# Schematic.net
KiCad netlist of a schematic drawn in Altium Designer
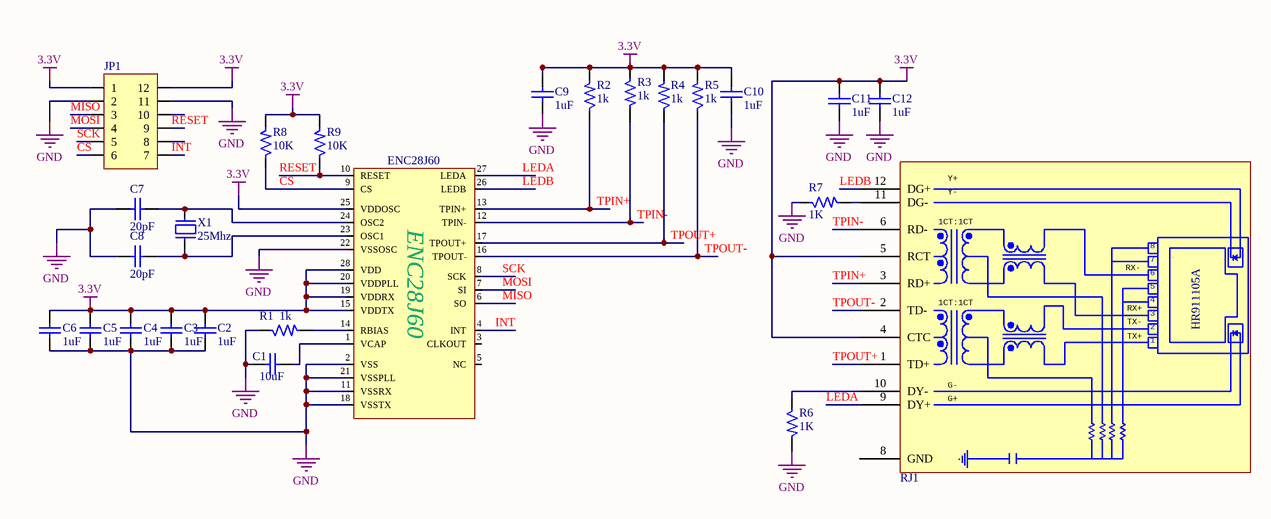
[diagram p0: Schematic.SchDoc]

(export (version "E")
  (design (tool "Eeschema 10.0.6"))
  (components
    (comp (ref "C1")
      (value "10uF")
      (footprint "CAP_0805")
      (description "Capacitor")
      (fields (field (name "PUBLISHER") "Altium Limited"))
      (libsource (lib "library") (part "CapSMD"))
    )
    (comp (ref "C2")
      (value "1uF")
      (footprint "CAP_0805")
      (description "Capacitor")
      (fields (field (name "PUBLISHER") "Altium Limited"))
      (libsource (lib "library") (part "CapSMD"))
    )
    (comp (ref "C3")
      (value "1uF")
      (footprint "CAP_0805")
      (description "Capacitor")
      (fields (field (name "PUBLISHER") "Altium Limited"))
      (libsource (lib "library") (part "CapSMD"))
    )
    (comp (ref "C4")
      (value "1uF")
      (footprint "CAP_0805")
      (description "Capacitor")
      (fields (field (name "PUBLISHER") "Altium Limited"))
      (libsource (lib "library") (part "CapSMD"))
    )
    (comp (ref "C5")
      (value "1uF")
      (footprint "CAP_0805")
      (description "Capacitor")
      (fields (field (name "PUBLISHER") "Altium Limited"))
      (libsource (lib "library") (part "CapSMD"))
    )
    (comp (ref "C6")
      (value "1uF")
      (footprint "CAP_0805")
      (description "Capacitor")
      (fields (field (name "PUBLISHER") "Altium Limited"))
      (libsource (lib "library") (part "CapSMD"))
    )
    (comp (ref "C7")
      (value "20pF")
      (footprint "CAP_0805")
      (description "Capacitor")
      (fields (field (name "PUBLISHER") "Altium Limited"))
      (libsource (lib "library") (part "CapSMD"))
    )
    (comp (ref "C8")
      (value "20pF")
      (footprint "CAP_0805")
      (description "Capacitor")
      (fields (field (name "PUBLISHER") "Altium Limited"))
      (libsource (lib "library") (part "CapSMD"))
    )
    (comp (ref "C9")
      (value "1uF")
      (footprint "CAP_0805")
      (description "Capacitor")
      (fields (field (name "PUBLISHER") "Altium Limited"))
      (libsource (lib "library") (part "CapSMD"))
    )
    (comp (ref "C10")
      (value "1uF")
      (footprint "CAP_0805")
      (description "Capacitor")
      (fields (field (name "PUBLISHER") "Altium Limited"))
      (libsource (lib "library") (part "CapSMD"))
    )
    (comp (ref "C11")
      (value "1uF")
      (footprint "CAP_0805")
      (description "Capacitor")
      (fields (field (name "PUBLISHER") "Altium Limited"))
      (libsource (lib "library") (part "CapSMD"))
    )
    (comp (ref "C12")
      (value "1uF")
      (footprint "CAP_0805")
      (description "Capacitor")
      (fields (field (name "PUBLISHER") "Altium Limited"))
      (libsource (lib "library") (part "CapSMD"))
    )
    (comp (ref "ENC28J60")
      (value "ENC28J60?")
      (footprint "SOP_28M_127")
      (libsource (lib "library") (part "ENC28J60"))
    )
    (comp (ref "JP1")
      (value "JP6x2")
      (footprint "JP6-D2T")
      (description "WR-PHD 2.54 mm Dual Socket Header")
      (fields
        (field (name "MANUFACTURER") "Würth Elektronik eiSos GmbH")
        (field (name "PARTNO") "61301221821")
        (field (name "CREATED BY") "Karrer Zheng")
      )
      (libsource (lib "LIBRARY") (part "JP6x2"))
    )
    (comp (ref "R1")
      (value "1k")
      (footprint "RES_0805")
      (description "Resistor 1/4W")
      (libsource (lib "library") (part "Res_0805"))
    )
    (comp (ref "R2")
      (value "1k")
      (footprint "RES_0805")
      (description "Resistor 1/4W")
      (libsource (lib "library") (part "Res_0805"))
    )
    (comp (ref "R3")
      (value "1k")
      (footprint "RES_0805")
      (description "Resistor 1/4W")
      (libsource (lib "library") (part "Res_0805"))
    )
    (comp (ref "R4")
      (value "1k")
      (footprint "RES_0805")
      (description "Resistor 1/4W")
      (libsource (lib "library") (part "Res_0805"))
    )
    (comp (ref "R5")
      (value "1k")
      (footprint "RES_0805")
      (description "Resistor 1/4W")
      (libsource (lib "library") (part "Res_0805"))
    )
    (comp (ref "R6")
      (value "1K")
      (footprint "RES_0805")
      (description "Resistor 1/4W")
      (libsource (lib "library") (part "Res_0805"))
    )
    (comp (ref "R7")
      (value "1K")
      (footprint "RES_0805")
      (description "Resistor 1/4W")
      (libsource (lib "library") (part "Res_0805"))
    )
    (comp (ref "R8")
      (value "10K")
      (footprint "RES_0805")
      (description "Resistor 1/4W")
      (libsource (lib "library") (part "Res_0805"))
    )
    (comp (ref "R9")
      (value "10K")
      (footprint "RES_0805")
      (description "Resistor 1/4W")
      (libsource (lib "library") (part "Res_0805"))
    )
    (comp (ref "RJ1") (value "RJ45") (footprint "RJ45") (libsource (lib "library") (part "RJ45-Con")))
    (comp (ref "X1")
      (value "25Mhz")
      (footprint "XT2")
      (description "Crystal, 32.768 KHz, -40 to 85 degC, 3.2 x 1.5 x 0.9 mm SMD")
      (libsource (lib "LIBRARY") (part "XT2"))
    )
  )
  (nets
    (net (code "2") (name "/CS") (class "Default")
      (node (ref "ENC28J60") (pin "9") (pinfunction "CS_9") (pintype "passive"))
      (node (ref "JP1") (pin "6") (pinfunction "6_6") (pintype "passive"))
      (node (ref "R8") (pin "1") (pinfunction "1_1") (pintype "passive"))
    )
    (net (code "3") (name "/INT") (class "Default")
      (node (ref "ENC28J60") (pin "4") (pinfunction "INT_4") (pintype "passive"))
      (node (ref "JP1") (pin "7") (pinfunction "7_7") (pintype "passive"))
    )
    (net (code "4") (name "/LEDA") (class "Default")
      (node (ref "ENC28J60") (pin "27") (pinfunction "LEDA_27") (pintype "passive"))
      (node (ref "RJ1") (pin "9") (pinfunction "DY+_9") (pintype "passive"))
    )
    (net (code "5") (name "/LEDB") (class "Default")
      (node (ref "ENC28J60") (pin "26") (pinfunction "LEDB_26") (pintype "passive"))
      (node (ref "RJ1") (pin "12") (pinfunction "DG+_12") (pintype "passive"))
    )
    (net (code "6") (name "/MISO") (class "Default")
      (node (ref "ENC28J60") (pin "6") (pinfunction "SO_6") (pintype "passive"))
      (node (ref "JP1") (pin "3") (pinfunction "3_3") (pintype "passive"))
    )
    (net (code "7") (name "/MOSI") (class "Default")
      (node (ref "ENC28J60") (pin "7") (pinfunction "SI_7") (pintype "passive"))
      (node (ref "JP1") (pin "4") (pinfunction "4_4") (pintype "passive"))
    )
    (net (code "8") (name "/RESET") (class "Default")
      (node (ref "ENC28J60") (pin "10") (pinfunction "RESET_10") (pintype "passive"))
      (node (ref "JP1") (pin "9") (pinfunction "9_9") (pintype "passive"))
      (node (ref "R9") (pin "1") (pinfunction "1_1") (pintype "passive"))
    )
    (net (code "9") (name "/SCK") (class "Default")
      (node (ref "ENC28J60") (pin "8") (pinfunction "SCK_8") (pintype "passive"))
      (node (ref "JP1") (pin "5") (pinfunction "5_5") (pintype "passive"))
    )
    (net (code "10") (name "/TPIN+") (class "Default")
      (node (ref "ENC28J60") (pin "13") (pinfunction "TPIN+_13") (pintype "passive"))
      (node (ref "R2") (pin "1") (pinfunction "1_1") (pintype "passive"))
      (node (ref "RJ1") (pin "3") (pinfunction "RD+_3") (pintype "passive"))
    )
    (net (code "11") (name "/TPIN-") (class "Default")
      (node (ref "ENC28J60") (pin "12") (pinfunction "TPIN-_12") (pintype "passive"))
      (node (ref "R3") (pin "2") (pinfunction "2_2") (pintype "passive"))
      (node (ref "RJ1") (pin "6") (pinfunction "RD-_6") (pintype "passive"))
    )
    (net (code "12") (name "/TPOUT+") (class "Default")
      (node (ref "ENC28J60") (pin "17") (pinfunction "TPOUT+_17") (pintype "passive"))
      (node (ref "R4") (pin "1") (pinfunction "1_1") (pintype "passive"))
      (node (ref "RJ1") (pin "1") (pinfunction "TD+_1") (pintype "passive"))
    )
    (net (code "13") (name "/TPOUT-") (class "Default")
      (node (ref "ENC28J60") (pin "16") (pinfunction "TPOUT-_16") (pintype "passive"))
      (node (ref "R5") (pin "1") (pinfunction "1_1") (pintype "passive"))
      (node (ref "RJ1") (pin "2") (pinfunction "TD-_2") (pintype "passive"))
    )
    (net (code "14") (name "3.3V") (class "Default")
      (node (ref "C10") (pin "1") (pinfunction "1_1") (pintype "passive"))
      (node (ref "C11") (pin "1") (pinfunction "1_1") (pintype "passive"))
      (node (ref "C12") (pin "1") (pinfunction "1_1") (pintype "passive"))
      (node (ref "C2") (pin "1") (pinfunction "1_1") (pintype "passive"))
      (node (ref "C3") (pin "1") (pinfunction "1_1") (pintype "passive"))
      (node (ref "C4") (pin "2") (pinfunction "2_2") (pintype "passive"))
      (node (ref "C5") (pin "1") (pinfunction "1_1") (pintype "passive"))
      (node (ref "C6") (pin "1") (pinfunction "1_1") (pintype "passive"))
      (node (ref "C9") (pin "2") (pinfunction "2_2") (pintype "passive"))
      (node (ref "ENC28J60") (pin "15") (pinfunction "VDDTX_15") (pintype "passive"))
      (node (ref "ENC28J60") (pin "19") (pinfunction "VDDRX_19") (pintype "passive"))
      (node (ref "ENC28J60") (pin "20") (pinfunction "VDDPLL_20") (pintype "passive"))
      (node (ref "ENC28J60") (pin "25") (pinfunction "VDDOSC_25") (pintype "passive"))
      (node (ref "ENC28J60") (pin "28") (pinfunction "VDD_28") (pintype "passive"))
      (node (ref "JP1") (pin "1") (pinfunction "1_1") (pintype "passive"))
      (node (ref "JP1") (pin "12") (pinfunction "12_12") (pintype "passive"))
      (node (ref "R2") (pin "2") (pinfunction "2_2") (pintype "passive"))
      (node (ref "R3") (pin "1") (pinfunction "1_1") (pintype "passive"))
      (node (ref "R4") (pin "2") (pinfunction "2_2") (pintype "passive"))
      (node (ref "R5") (pin "2") (pinfunction "2_2") (pintype "passive"))
      (node (ref "R8") (pin "2") (pinfunction "2_2") (pintype "passive"))
      (node (ref "R9") (pin "2") (pinfunction "2_2") (pintype "passive"))
      (node (ref "RJ1") (pin "4") (pinfunction "CTC_4") (pintype "passive"))
      (node (ref "RJ1") (pin "5") (pinfunction "RCT_5") (pintype "passive"))
    )
    (net (code "15") (name "GND") (class "Default")
      (node (ref "C1") (pin "1") (pinfunction "1_1") (pintype "passive"))
      (node (ref "C10") (pin "2") (pinfunction "2_2") (pintype "passive"))
      (node (ref "C11") (pin "2") (pinfunction "2_2") (pintype "passive"))
      (node (ref "C12") (pin "2") (pinfunction "2_2") (pintype "passive"))
      (node (ref "C2") (pin "2") (pinfunction "2_2") (pintype "passive"))
      (node (ref "C3") (pin "2") (pinfunction "2_2") (pintype "passive"))
      (node (ref "C4") (pin "1") (pinfunction "1_1") (pintype "passive"))
      (node (ref "C5") (pin "2") (pinfunction "2_2") (pintype "passive"))
      (node (ref "C6") (pin "2") (pinfunction "2_2") (pintype "passive"))
      (node (ref "C7") (pin "1") (pinfunction "1_1") (pintype "passive"))
      (node (ref "C8") (pin "1") (pinfunction "1_1") (pintype "passive"))
      (node (ref "C9") (pin "1") (pinfunction "1_1") (pintype "passive"))
      (node (ref "ENC28J60") (pin "11") (pinfunction "VSSRX_11") (pintype "passive"))
      (node (ref "ENC28J60") (pin "18") (pinfunction "VSSTX_18") (pintype "passive"))
      (node (ref "ENC28J60") (pin "2") (pinfunction "VSS_2") (pintype "passive"))
      (node (ref "ENC28J60") (pin "21") (pinfunction "VSSPLL_21") (pintype "passive"))
      (node (ref "ENC28J60") (pin "22") (pinfunction "VSSOSC_22") (pintype "passive"))
      (node (ref "JP1") (pin "11") (pinfunction "11_11") (pintype "passive"))
      (node (ref "JP1") (pin "2") (pinfunction "2_2") (pintype "passive"))
      (node (ref "R1") (pin "1") (pinfunction "1_1") (pintype "passive"))
      (node (ref "R6") (pin "2") (pinfunction "2_2") (pintype "passive"))
      (node (ref "R7") (pin "1") (pinfunction "1_1") (pintype "passive"))
    )
    (net (code "16") (name "Net-(ENC28J60-OSC1)") (class "Default")
      (node (ref "C8") (pin "2") (pinfunction "2_2") (pintype "passive"))
      (node (ref "ENC28J60") (pin "23") (pinfunction "OSC1_23") (pintype "passive"))
      (node (ref "X1") (pin "1") (pinfunction "1_1") (pintype "passive"))
    )
    (net (code "17") (name "Net-(ENC28J60-OSC2)") (class "Default")
      (node (ref "C7") (pin "2") (pinfunction "2_2") (pintype "passive"))
      (node (ref "ENC28J60") (pin "24") (pinfunction "OSC2_24") (pintype "passive"))
      (node (ref "X1") (pin "2") (pinfunction "2_2") (pintype "passive"))
    )
    (net (code "18") (name "Net-(ENC28J60-RBIAS)") (class "Default")
      (node (ref "ENC28J60") (pin "14") (pinfunction "RBIAS_14") (pintype "passive"))
      (node (ref "R1") (pin "2") (pinfunction "2_2") (pintype "passive"))
    )
    (net (code "19") (name "Net-(ENC28J60-VCAP)") (class "Default")
      (node (ref "C1") (pin "2") (pinfunction "2_2") (pintype "passive"))
      (node (ref "ENC28J60") (pin "1") (pinfunction "VCAP_1") (pintype "passive"))
    )
    (net (code "20") (name "Net-(RJ1-DG-)") (class "Default")
      (node (ref "R7") (pin "2") (pinfunction "2_2") (pintype "passive"))
      (node (ref "RJ1") (pin "11") (pinfunction "DG-_11") (pintype "passive"))
    )
    (net (code "21") (name "Net-(RJ1-DY-)") (class "Default")
      (node (ref "R6") (pin "1") (pinfunction "1_1") (pintype "passive"))
      (node (ref "RJ1") (pin "10") (pinfunction "DY-_10") (pintype "passive"))
    )
    (net (code "22") (name "unconnected-(ENC28J60-CLKOUT-Pad3)") (class "Default")
      (node (ref "ENC28J60") (pin "3") (pinfunction "CLKOUT_3") (pintype "passive"))
    )
    (net (code "23") (name "unconnected-(ENC28J60-NC-Pad5)") (class "Default")
      (node (ref "ENC28J60") (pin "5") (pinfunction "NC_5") (pintype "passive"))
    )
    (net (code "24") (name "unconnected-(JP1-Pad8)") (class "Default")
      (node (ref "JP1") (pin "8") (pinfunction "8_8") (pintype "passive"))
    )
    (net (code "25") (name "unconnected-(JP1-Pad10)") (class "Default")
      (node (ref "JP1") (pin "10") (pinfunction "10_10") (pintype "passive"))
    )
    (net (code "26") (name "unconnected-(RJ1-GND-Pad8)") (class "Default")
      (node (ref "RJ1") (pin "8") (pinfunction "GND_8") (pintype "power_in"))
    )
  )
)
